# joystick_board_esp32_2025-03-03.net
KiCad netlist of a schematic drawn in EasyEDA Pro
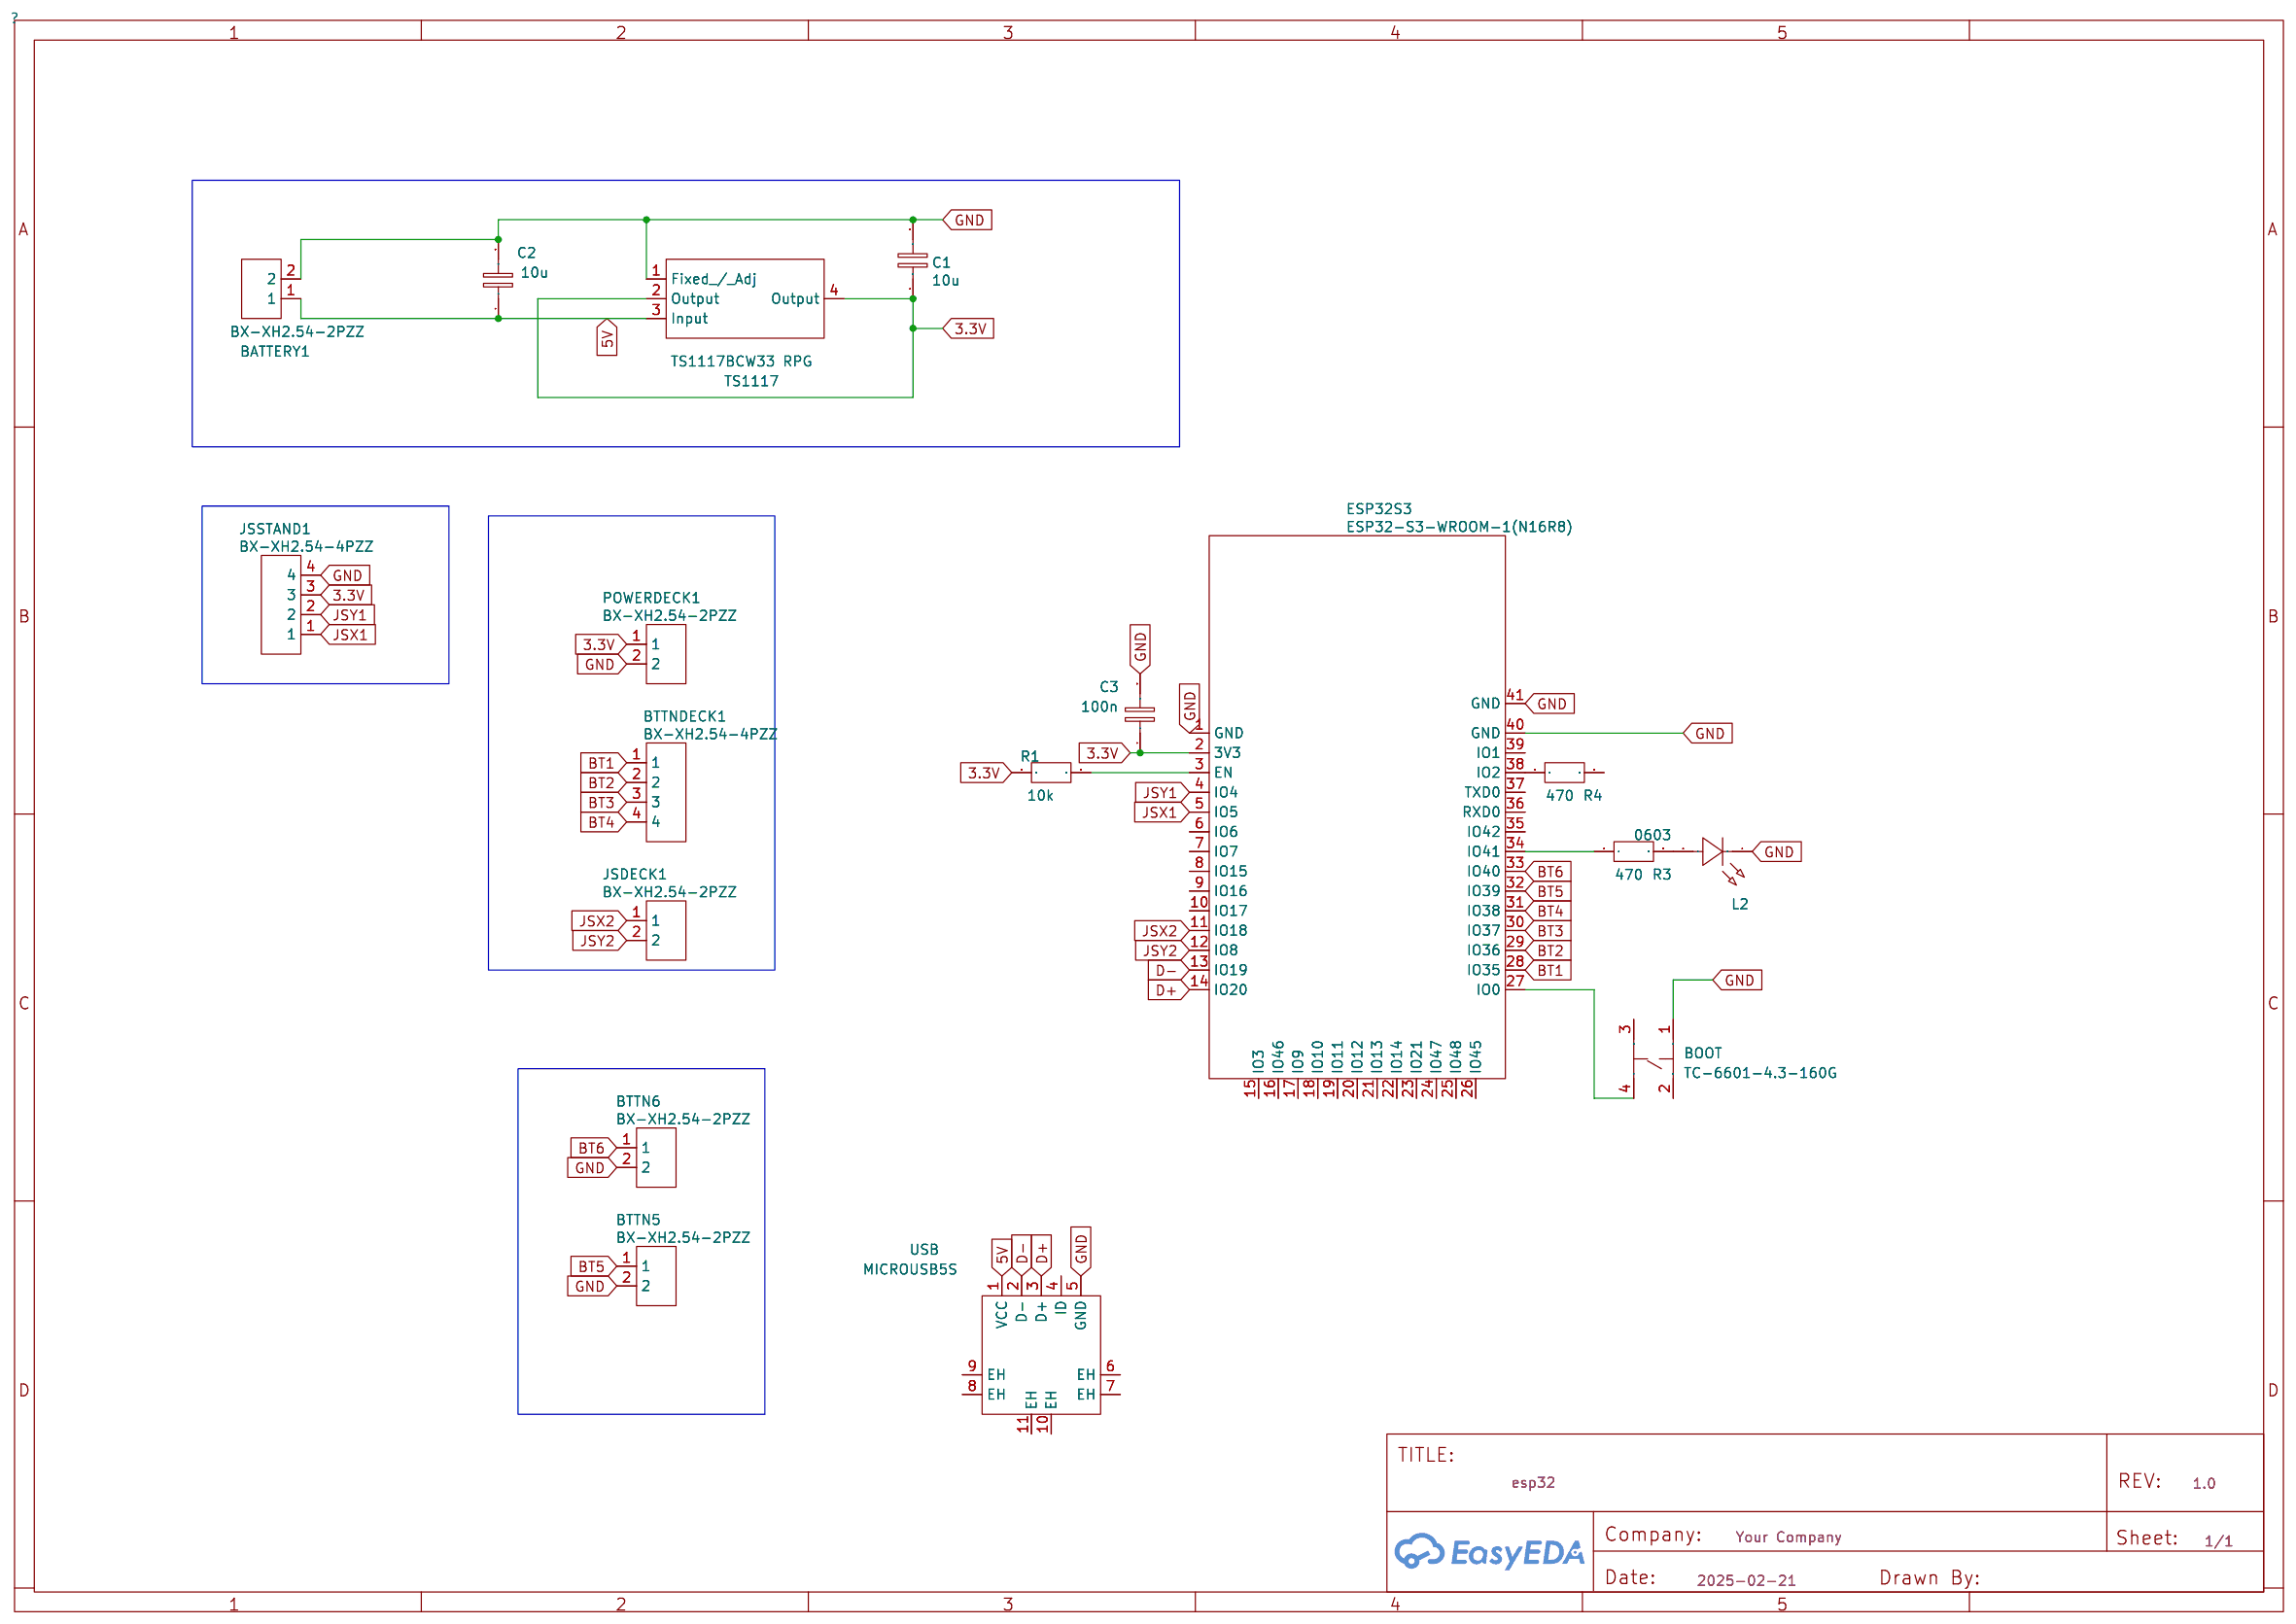
[diagram p0: schematic sheet]

(export (version "E")
  (design (tool "Eeschema 10.0.6"))
  (components
    (comp (ref "BATTERY1")
      (value "BX-XH2.54-2PZZ")
      (footprint "easyedapro:CONN-TH_2P-P2.50_BX-XH2.54-2PZZ")
      (fields (field (name "Manufacturer") "Bossie(博锡)"))
      (libsource (lib "") (part "BX-XH2.54-2PZZ_1"))
    )
    (comp (ref "BOOT")
      (value "TC-6601-4.3-160G")
      (footprint "easyedapro:SW-SMD_4P-L6.0-W6.0-P4.50-LS10.0_HCTL_TC-6601-XX")
      (fields (field (name "Manufacturer") "HCTL(华灿天禄)"))
      (libsource (lib "easyedapro") (part "TC-6601-4.3-160G"))
    )
    (comp (ref "BTTN5")
      (value "BX-XH2.54-2PZZ")
      (footprint "easyedapro:CONN-TH_2P-P2.50_BX-XH2.54-2PZZ")
      (fields (field (name "Manufacturer") "Bossie(博锡)"))
      (libsource (lib "easyedapro") (part "BX-XH2.54-2PZZ"))
    )
    (comp (ref "BTTN6")
      (value "BX-XH2.54-2PZZ")
      (footprint "easyedapro:CONN-TH_2P-P2.50_BX-XH2.54-2PZZ")
      (fields (field (name "Manufacturer") "Bossie(博锡)"))
      (libsource (lib "easyedapro") (part "BX-XH2.54-2PZZ"))
    )
    (comp (ref "BTTNDECK1")
      (value "BX-XH2.54-4PZZ")
      (footprint "easyedapro:CONN-TH_4P-P2.50_BX-XH2.54-4PZZ")
      (fields (field (name "Manufacturer") "Bossie(博锡)"))
      (libsource (lib "easyedapro") (part "BX-XH2.54-4PZZ"))
    )
    (comp (ref "C1") (value "10u") (footprint "easyedapro:C0603") (libsource (lib "easyedapro") (part "10u")))
    (comp (ref "C2") (value "10u") (footprint "easyedapro:C0603") (libsource (lib "easyedapro") (part "10u")))
    (comp (ref "C3")
      (value "100n")
      (footprint "easyedapro:C0603")
      (libsource (lib "easyedapro") (part "100n"))
    )
    (comp (ref "ESP32S3")
      (value "ESP32-S3-WROOM-1(N16R8)")
      (footprint "easyedapro:WIRELM-SMD_ESP32-S3-WROOM-1")
      (fields
        (field (name "Manufacturer Part") "ESP32-S3-WROOM-1-N16R8")
        (field (name "Manufacturer") "ESPRESSIF(乐鑫)")
      )
      (libsource (lib "easyedapro") (part "ESP32-S3-WROOM-1(N16R8)"))
    )
    (comp (ref "JSDECK1")
      (value "BX-XH2.54-2PZZ")
      (footprint "easyedapro:CONN-TH_2P-P2.50_BX-XH2.54-2PZZ")
      (fields (field (name "Manufacturer") "Bossie(博锡)"))
      (libsource (lib "easyedapro") (part "BX-XH2.54-2PZZ"))
    )
    (comp (ref "JSSTAND1")
      (value "BX-XH2.54-4PZZ")
      (footprint "easyedapro:CONN-TH_4P-P2.50_BX-XH2.54-4PZZ")
      (fields (field (name "Manufacturer") "Bossie(博锡)"))
      (libsource (lib "") (part "BX-XH2.54-4PZZ_1"))
    )
    (comp (ref "L2")
      (value "0603")
      (footprint "easyedapro:LED0603-RD_RED")
      (libsource (lib "easyedapro") (part "0603"))
    )
    (comp (ref "POWERDECK1")
      (value "BX-XH2.54-2PZZ")
      (footprint "easyedapro:CONN-TH_2P-P2.50_BX-XH2.54-2PZZ")
      (fields (field (name "Manufacturer") "Bossie(博锡)"))
      (libsource (lib "easyedapro") (part "BX-XH2.54-2PZZ"))
    )
    (comp (ref "R1") (value "10k") (footprint "easyedapro:R0603") (libsource (lib "easyedapro") (part "10k")))
    (comp (ref "R3") (value "470") (footprint "easyedapro:R0603") (libsource (lib "easyedapro") (part "470")))
    (comp (ref "R4") (value "470") (footprint "easyedapro:R0603") (libsource (lib "easyedapro") (part "470")))
    (comp (ref "TS1117")
      (value "TS1117BCW33 RPG")
      (footprint "easyedapro:SOT-223_L6.5-W3.5-P2.30-LS7.0-BR")
      (fields (field (name "Manufacturer") "Taiwan Semiconductor(台湾半导体)"))
      (libsource (lib "easyedapro") (part "TS1117BCW33 RPG"))
    )
    (comp (ref "USB")
      (value "MICROUSB5S")
      (footprint "easyedapro:MICRO-USB_MICRO-USB-5S")
      (libsource (lib "easyedapro") (part "MICROUSB5S"))
    )
  )
  (nets
    (net (code "1") (name "3.3V") (class "Default")
      (node (ref "C1") (pin "1") (pinfunction "1_1") (pintype "unspecified"))
      (node (ref "C3") (pin "1") (pinfunction "1_1") (pintype "unspecified"))
      (node (ref "ESP32S3") (pin "2") (pinfunction "3V3_2") (pintype "unspecified"))
      (node (ref "JSSTAND1") (pin "3") (pinfunction "3_3") (pintype "unspecified"))
      (node (ref "POWERDECK1") (pin "1") (pinfunction "1_1") (pintype "unspecified"))
      (node (ref "R1") (pin "1") (pinfunction "1_1") (pintype "unspecified"))
      (node (ref "TS1117") (pin "2") (pinfunction "Output_2") (pintype "unspecified"))
      (node (ref "TS1117") (pin "4") (pinfunction "Output_4") (pintype "unspecified"))
    )
    (net (code "2") (name "5V") (class "Default")
      (node (ref "BATTERY1") (pin "1") (pinfunction "1_1") (pintype "unspecified"))
      (node (ref "C2") (pin "1") (pinfunction "1_1") (pintype "unspecified"))
      (node (ref "TS1117") (pin "3") (pinfunction "Input_3") (pintype "unspecified"))
      (node (ref "USB") (pin "1") (pinfunction "VCC_1") (pintype "input"))
    )
    (net (code "3") (name "BT1") (class "Default")
      (node (ref "BTTNDECK1") (pin "1") (pinfunction "1_1") (pintype "unspecified"))
      (node (ref "ESP32S3") (pin "28") (pinfunction "IO35_28") (pintype "unspecified"))
    )
    (net (code "4") (name "BT2") (class "Default")
      (node (ref "BTTNDECK1") (pin "2") (pinfunction "2_2") (pintype "unspecified"))
      (node (ref "ESP32S3") (pin "29") (pinfunction "IO36_29") (pintype "unspecified"))
    )
    (net (code "5") (name "BT3") (class "Default")
      (node (ref "BTTNDECK1") (pin "3") (pinfunction "3_3") (pintype "unspecified"))
      (node (ref "ESP32S3") (pin "30") (pinfunction "IO37_30") (pintype "unspecified"))
    )
    (net (code "6") (name "BT4") (class "Default")
      (node (ref "BTTNDECK1") (pin "4") (pinfunction "4_4") (pintype "unspecified"))
      (node (ref "ESP32S3") (pin "31") (pinfunction "IO38_31") (pintype "unspecified"))
    )
    (net (code "7") (name "BT5") (class "Default")
      (node (ref "BTTN5") (pin "1") (pinfunction "1_1") (pintype "unspecified"))
      (node (ref "ESP32S3") (pin "32") (pinfunction "IO39_32") (pintype "unspecified"))
    )
    (net (code "8") (name "BT6") (class "Default")
      (node (ref "BTTN6") (pin "1") (pinfunction "1_1") (pintype "unspecified"))
      (node (ref "ESP32S3") (pin "33") (pinfunction "IO40_33") (pintype "unspecified"))
    )
    (net (code "9") (name "D+") (class "Default")
      (node (ref "ESP32S3") (pin "14") (pinfunction "IO20_14") (pintype "unspecified"))
      (node (ref "USB") (pin "3") (pinfunction "D+_3") (pintype "input"))
    )
    (net (code "10") (name "D-") (class "Default")
      (node (ref "ESP32S3") (pin "13") (pinfunction "IO19_13") (pintype "unspecified"))
      (node (ref "USB") (pin "2") (pinfunction "D-_2") (pintype "input"))
    )
    (net (code "11") (name "GND") (class "Default")
      (node (ref "BATTERY1") (pin "2") (pinfunction "2_2") (pintype "unspecified"))
      (node (ref "BOOT") (pin "1") (pinfunction "1_1") (pintype "unspecified"))
      (node (ref "BTTN5") (pin "2") (pinfunction "2_2") (pintype "unspecified"))
      (node (ref "BTTN6") (pin "2") (pinfunction "2_2") (pintype "unspecified"))
      (node (ref "C1") (pin "2") (pinfunction "2_2") (pintype "unspecified"))
      (node (ref "C2") (pin "2") (pinfunction "2_2") (pintype "unspecified"))
      (node (ref "C3") (pin "2") (pinfunction "2_2") (pintype "unspecified"))
      (node (ref "ESP32S3") (pin "1") (pinfunction "GND_1") (pintype "unspecified"))
      (node (ref "ESP32S3") (pin "40") (pinfunction "GND_40") (pintype "unspecified"))
      (node (ref "ESP32S3") (pin "41") (pinfunction "GND_41") (pintype "unspecified"))
      (node (ref "JSSTAND1") (pin "4") (pinfunction "4_4") (pintype "unspecified"))
      (node (ref "L2") (pin "1") (pinfunction "K_1") (pintype "unspecified"))
      (node (ref "POWERDECK1") (pin "2") (pinfunction "2_2") (pintype "unspecified"))
      (node (ref "TS1117") (pin "1") (pinfunction "Fixed_/_Adj_1") (pintype "unspecified"))
      (node (ref "USB") (pin "5") (pinfunction "GND_5") (pintype "input"))
    )
    (net (code "12") (name "JSX1") (class "Default")
      (node (ref "ESP32S3") (pin "5") (pinfunction "IO5_5") (pintype "unspecified"))
      (node (ref "JSSTAND1") (pin "1") (pinfunction "1_1") (pintype "unspecified"))
    )
    (net (code "13") (name "JSX2") (class "Default")
      (node (ref "ESP32S3") (pin "11") (pinfunction "IO18_11") (pintype "unspecified"))
      (node (ref "JSDECK1") (pin "1") (pinfunction "1_1") (pintype "unspecified"))
    )
    (net (code "14") (name "JSY1") (class "Default")
      (node (ref "ESP32S3") (pin "4") (pinfunction "IO4_4") (pintype "unspecified"))
      (node (ref "JSSTAND1") (pin "2") (pinfunction "2_2") (pintype "unspecified"))
    )
    (net (code "15") (name "JSY2") (class "Default")
      (node (ref "ESP32S3") (pin "12") (pinfunction "IO8_12") (pintype "unspecified"))
      (node (ref "JSDECK1") (pin "2") (pinfunction "2_2") (pintype "unspecified"))
    )
    (net (code "16") (name "Net-(ESP32S3-EN)") (class "Default")
      (node (ref "ESP32S3") (pin "3") (pinfunction "EN_3") (pintype "unspecified"))
      (node (ref "R1") (pin "2") (pinfunction "2_2") (pintype "unspecified"))
    )
    (net (code "17") (name "Net-(ESP32S3-IO0)") (class "Default")
      (node (ref "BOOT") (pin "4") (pinfunction "4_4") (pintype "unspecified"))
      (node (ref "ESP32S3") (pin "27") (pinfunction "IO0_27") (pintype "unspecified"))
    )
    (net (code "18") (name "Net-(ESP32S3-IO2)") (class "Default")
      (node (ref "ESP32S3") (pin "38") (pinfunction "IO2_38") (pintype "unspecified"))
      (node (ref "R4") (pin "1") (pinfunction "1_1") (pintype "unspecified"))
    )
    (net (code "19") (name "Net-(ESP32S3-IO41)") (class "Default")
      (node (ref "ESP32S3") (pin "34") (pinfunction "IO41_34") (pintype "unspecified"))
      (node (ref "R3") (pin "1") (pinfunction "1_1") (pintype "unspecified"))
    )
    (net (code "20") (name "Net-(L2-A)") (class "Default")
      (node (ref "L2") (pin "2") (pinfunction "A_2") (pintype "unspecified"))
      (node (ref "R3") (pin "2") (pinfunction "2_2") (pintype "unspecified"))
    )
    (net (code "21") (name "unconnected-(BOOT-Pad2)") (class "Default")
      (node (ref "BOOT") (pin "2") (pinfunction "2_2") (pintype "unspecified"))
    )
    (net (code "22") (name "unconnected-(BOOT-Pad3)") (class "Default")
      (node (ref "BOOT") (pin "3") (pinfunction "3_3") (pintype "unspecified"))
    )
    (net (code "23") (name "unconnected-(ESP32S3-IO1-Pad39)") (class "Default")
      (node (ref "ESP32S3") (pin "39") (pinfunction "IO1_39") (pintype "unspecified"))
    )
    (net (code "24") (name "unconnected-(ESP32S3-IO3-Pad15)") (class "Default")
      (node (ref "ESP32S3") (pin "15") (pinfunction "IO3_15") (pintype "unspecified"))
    )
    (net (code "25") (name "unconnected-(ESP32S3-IO6-Pad6)") (class "Default")
      (node (ref "ESP32S3") (pin "6") (pinfunction "IO6_6") (pintype "unspecified"))
    )
    (net (code "26") (name "unconnected-(ESP32S3-IO7-Pad7)") (class "Default")
      (node (ref "ESP32S3") (pin "7") (pinfunction "IO7_7") (pintype "unspecified"))
    )
    (net (code "27") (name "unconnected-(ESP32S3-IO9-Pad17)") (class "Default")
      (node (ref "ESP32S3") (pin "17") (pinfunction "IO9_17") (pintype "unspecified"))
    )
    (net (code "28") (name "unconnected-(ESP32S3-IO10-Pad18)") (class "Default")
      (node (ref "ESP32S3") (pin "18") (pinfunction "IO10_18") (pintype "unspecified"))
    )
    (net (code "29") (name "unconnected-(ESP32S3-IO11-Pad19)") (class "Default")
      (node (ref "ESP32S3") (pin "19") (pinfunction "IO11_19") (pintype "unspecified"))
    )
    (net (code "30") (name "unconnected-(ESP32S3-IO12-Pad20)") (class "Default")
      (node (ref "ESP32S3") (pin "20") (pinfunction "IO12_20") (pintype "unspecified"))
    )
    (net (code "31") (name "unconnected-(ESP32S3-IO13-Pad21)") (class "Default")
      (node (ref "ESP32S3") (pin "21") (pinfunction "IO13_21") (pintype "unspecified"))
    )
    (net (code "32") (name "unconnected-(ESP32S3-IO14-Pad22)") (class "Default")
      (node (ref "ESP32S3") (pin "22") (pinfunction "IO14_22") (pintype "unspecified"))
    )
    (net (code "33") (name "unconnected-(ESP32S3-IO15-Pad8)") (class "Default")
      (node (ref "ESP32S3") (pin "8") (pinfunction "IO15_8") (pintype "unspecified"))
    )
    (net (code "34") (name "unconnected-(ESP32S3-IO16-Pad9)") (class "Default")
      (node (ref "ESP32S3") (pin "9") (pinfunction "IO16_9") (pintype "unspecified"))
    )
    (net (code "35") (name "unconnected-(ESP32S3-IO17-Pad10)") (class "Default")
      (node (ref "ESP32S3") (pin "10") (pinfunction "IO17_10") (pintype "unspecified"))
    )
    (net (code "36") (name "unconnected-(ESP32S3-IO21-Pad23)") (class "Default")
      (node (ref "ESP32S3") (pin "23") (pinfunction "IO21_23") (pintype "unspecified"))
    )
    (net (code "37") (name "unconnected-(ESP32S3-IO42-Pad35)") (class "Default")
      (node (ref "ESP32S3") (pin "35") (pinfunction "IO42_35") (pintype "unspecified"))
    )
    (net (code "38") (name "unconnected-(ESP32S3-IO45-Pad26)") (class "Default")
      (node (ref "ESP32S3") (pin "26") (pinfunction "IO45_26") (pintype "unspecified"))
    )
    (net (code "39") (name "unconnected-(ESP32S3-IO46-Pad16)") (class "Default")
      (node (ref "ESP32S3") (pin "16") (pinfunction "IO46_16") (pintype "unspecified"))
    )
    (net (code "40") (name "unconnected-(ESP32S3-IO47-Pad24)") (class "Default")
      (node (ref "ESP32S3") (pin "24") (pinfunction "IO47_24") (pintype "unspecified"))
    )
    (net (code "41") (name "unconnected-(ESP32S3-IO48-Pad25)") (class "Default")
      (node (ref "ESP32S3") (pin "25") (pinfunction "IO48_25") (pintype "unspecified"))
    )
    (net (code "42") (name "unconnected-(ESP32S3-RXD0-Pad36)") (class "Default")
      (node (ref "ESP32S3") (pin "36") (pinfunction "RXD0_36") (pintype "unspecified"))
    )
    (net (code "43") (name "unconnected-(ESP32S3-TXD0-Pad37)") (class "Default")
      (node (ref "ESP32S3") (pin "37") (pinfunction "TXD0_37") (pintype "unspecified"))
    )
    (net (code "44") (name "unconnected-(R4-Pad2)") (class "Default")
      (node (ref "R4") (pin "2") (pinfunction "2_2") (pintype "unspecified"))
    )
    (net (code "45") (name "unconnected-(USB-EH-Pad6)") (class "Default")
      (node (ref "USB") (pin "6") (pinfunction "EH_6") (pintype "unspecified"))
    )
    (net (code "46") (name "unconnected-(USB-EH-Pad7)") (class "Default")
      (node (ref "USB") (pin "7") (pinfunction "EH_7") (pintype "unspecified"))
    )
    (net (code "47") (name "unconnected-(USB-EH-Pad8)") (class "Default")
      (node (ref "USB") (pin "8") (pinfunction "EH_8") (pintype "unspecified"))
    )
    (net (code "48") (name "unconnected-(USB-EH-Pad9)") (class "Default")
      (node (ref "USB") (pin "9") (pinfunction "EH_9") (pintype "unspecified"))
    )
    (net (code "49") (name "unconnected-(USB-EH-Pad10)") (class "Default")
      (node (ref "USB") (pin "10") (pinfunction "EH_10") (pintype "unspecified"))
    )
    (net (code "50") (name "unconnected-(USB-EH-Pad11)") (class "Default")
      (node (ref "USB") (pin "11") (pinfunction "EH_11") (pintype "unspecified"))
    )
    (net (code "51") (name "unconnected-(USB-ID-Pad4)") (class "Default")
      (node (ref "USB") (pin "4") (pinfunction "ID_4") (pintype "input"))
    )
  )
)
